# 12-USB_Phy.net
KiCad netlist of a schematic drawn in Altium Designer
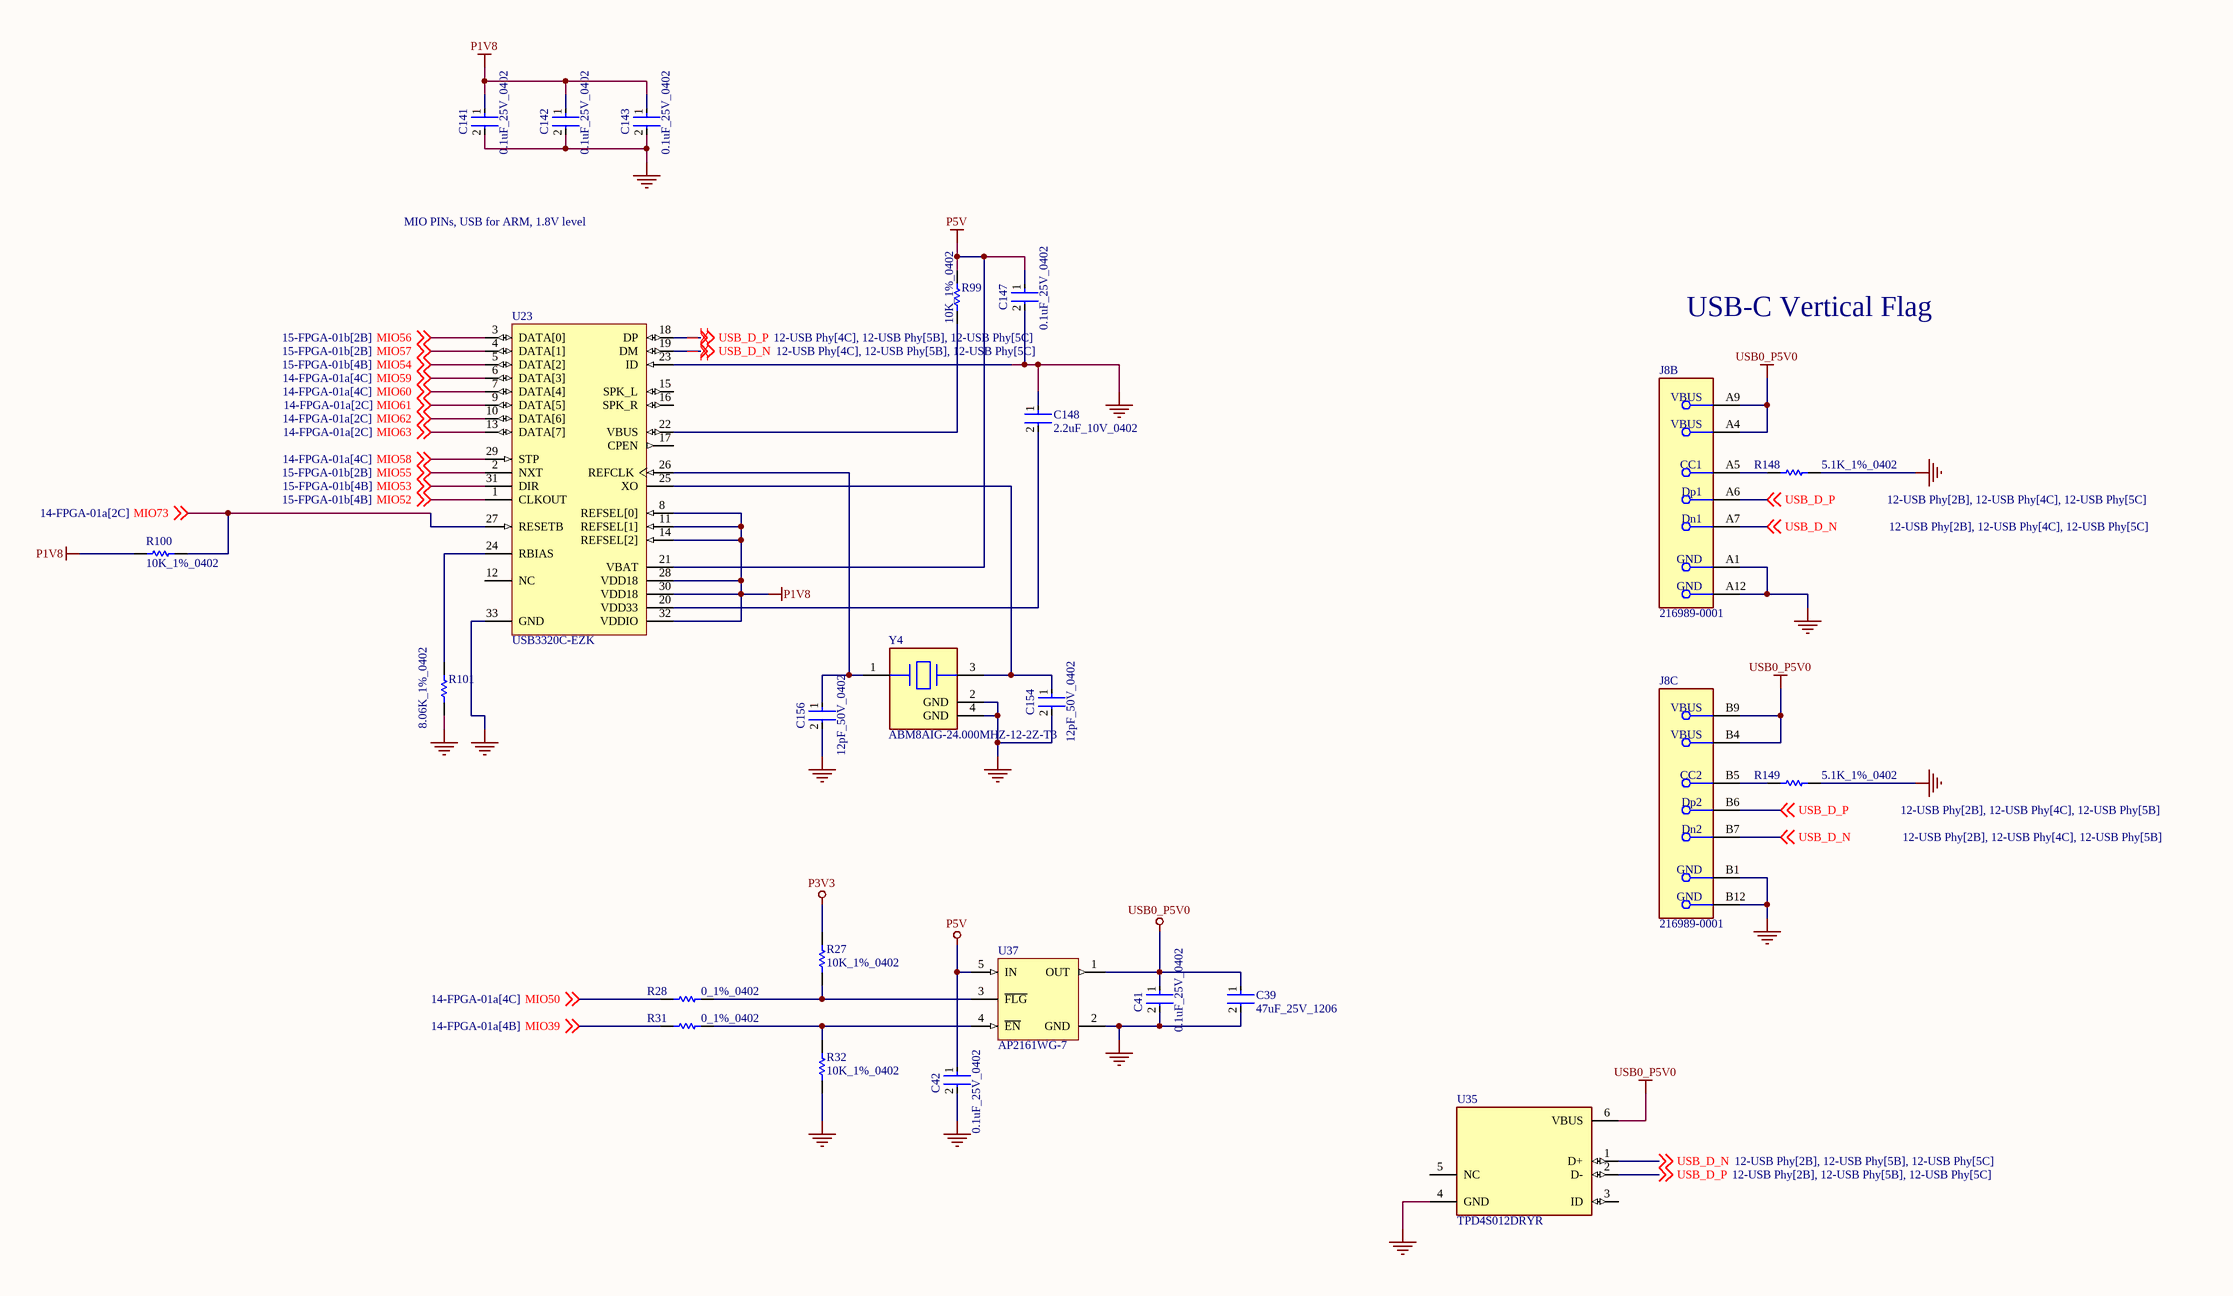
[diagram p0: 12-USB Phy.SchDoc]

(export (version "E")
  (design (tool "Eeschema 10.0.6"))
  (components
    (comp (ref "C39")
      (value "47uF_25V_1206")
      (footprint "FP-C3216-160-0_2-MFG")
      (description "Multilayer Ceramic Capacitors 47uF ±20% 25V X5R SMD 1206")
      (fields (field (name "VOLTAGE") "25V") (field (name "TOLERANCE") "20%"))
      (libsource (lib "Altium Content Vault") (part "11868f565c42a9108669ba33697ecf6"))
    )
    (comp (ref "C41")
      (value "0.1uF_25V_0402")
      (footprint "FP-0402-L_1_0_1-W_0_5_0_1-IPC_C")
      (description "General Purpose Ceramic Capacitor, 0402, 100nF, 10%, X7R, 15%, 25V")
      (fields (field (name "VOLTAGE") "25V") (field (name "TOLERANCE") "10%"))
      (libsource (lib "Altium Content Vault") (part "b4654b650e69147ec39a6b967a45e02"))
    )
    (comp (ref "C42")
      (value "0.1uF_25V_0402")
      (footprint "FP-0402-L_1_0_1-W_0_5_0_1-IPC_C")
      (description "General Purpose Ceramic Capacitor, 0402, 100nF, 10%, X7R, 15%, 25V")
      (fields (field (name "VOLTAGE") "25V") (field (name "TOLERANCE") "10%"))
      (libsource (lib "Altium Content Vault") (part "b4654b650e69147ec39a6b967a45e02"))
    )
    (comp (ref "C141")
      (value "0.1uF_25V_0402")
      (footprint "FP-0402-L_1_0_1-W_0_5_0_1-IPC_C")
      (description "General Purpose Ceramic Capacitor, 0402, 100nF, 10%, X7R, 15%, 25V")
      (fields (field (name "VOLTAGE") "25V") (field (name "TOLERANCE") "10%"))
      (libsource (lib "Altium Content Vault") (part "b4654b650e69147ec39a6b967a45e02"))
    )
    (comp (ref "C142")
      (value "0.1uF_25V_0402")
      (footprint "FP-0402-L_1_0_1-W_0_5_0_1-IPC_C")
      (description "General Purpose Ceramic Capacitor, 0402, 100nF, 10%, X7R, 15%, 25V")
      (fields (field (name "VOLTAGE") "25V") (field (name "TOLERANCE") "10%"))
      (libsource (lib "Altium Content Vault") (part "b4654b650e69147ec39a6b967a45e02"))
    )
    (comp (ref "C143")
      (value "0.1uF_25V_0402")
      (footprint "FP-0402-L_1_0_1-W_0_5_0_1-IPC_C")
      (description "General Purpose Ceramic Capacitor, 0402, 100nF, 10%, X7R, 15%, 25V")
      (fields (field (name "VOLTAGE") "25V") (field (name "TOLERANCE") "10%"))
      (libsource (lib "Altium Content Vault") (part "b4654b650e69147ec39a6b967a45e02"))
    )
    (comp (ref "C147")
      (value "0.1uF_25V_0402")
      (footprint "FP-0402-L_1_0_1-W_0_5_0_1-IPC_C")
      (description "General Purpose Ceramic Capacitor, 0402, 100nF, 10%, X7R, 15%, 25V")
      (fields (field (name "VOLTAGE") "25V") (field (name "TOLERANCE") "10%"))
      (libsource (lib "Altium Content Vault") (part "b4654b650e69147ec39a6b967a45e02"))
    )
    (comp (ref "C148")
      (value "2.2uF_10V_0402")
      (footprint "FP-C1005-050-0_15-0_1-MFG")
      (description "CAP CER 2.2UF 10V X7S 0402")
      (fields (field (name "TOLERANCE") "10%"))
      (libsource (lib "Altium Content Vault") (part "b4654b650e69147ec39a6b967a45e02"))
    )
    (comp (ref "C154")
      (value "12pF_50V_0402")
      (footprint "FP-0402-L_1_0_1-W_0_5_0_1-IPC_B")
      (description "General Purpose Ceramic Capacitor, 0402, 12pF, 5%, C0G, 30ppm/°C, 50V")
      (fields (field (name "VOLTAGE") "50V") (field (name "TOLERANCE") "5%"))
      (libsource (lib "Altium Content Vault") (part "b4654b650e69147ec39a6b967a45e02"))
    )
    (comp (ref "C156")
      (value "12pF_50V_0402")
      (footprint "FP-0402-L_1_0_1-W_0_5_0_1-IPC_B")
      (description "General Purpose Ceramic Capacitor, 0402, 12pF, 5%, C0G, 30ppm/°C, 50V")
      (fields (field (name "VOLTAGE") "50V") (field (name "TOLERANCE") "5%"))
      (libsource (lib "Altium Content Vault") (part "b4654b650e69147ec39a6b967a45e02"))
    )
    (comp (ref "J8")
      (value "216989-0001")
      (footprint "FP-216989-0001-MFG")
      (description "CONN RCPT USB2.0 TYPE C 24POS RA")
      (libsource (lib "Altium Content Vault") (part "0223f526f2db1734dda50670d79969c"))
    )
    (comp (ref "R27")
      (value "10K_1%_0402")
      (footprint "RESC1005X40X25NL10T10")
      (fields (field (name "MANUFACTURER") "Bourns") (field (name "PART NUMBER") "CR0402-FX-1002GLF"))
      (libsource (lib "Altium Content Vault") (part "RES"))
    )
    (comp (ref "R28")
      (value "0_1%_0402")
      (footprint "RESC1005X40X25LL05T05")
      (description "Chip Resistor, 0 Ohm, 0.1 W, -55 to 155 degC, 0402 (1005 Metric), RoHS, Tape and Reel")
      (fields (field (name "MANUFACTURER") "Panasonic") (field (name "TOLERANCE") "5%"))
      (libsource (lib "Altium Content Vault") (part "RES-2"))
    )
    (comp (ref "R31")
      (value "0_1%_0402")
      (footprint "RESC1005X40X25LL05T05")
      (description "Chip Resistor, 0 Ohm, 0.1 W, -55 to 155 degC, 0402 (1005 Metric), RoHS, Tape and Reel")
      (fields (field (name "MANUFACTURER") "Panasonic") (field (name "TOLERANCE") "5%"))
      (libsource (lib "Altium Content Vault") (part "RES-2"))
    )
    (comp (ref "R32")
      (value "10K_1%_0402")
      (footprint "RESC1005X40X25NL10T10")
      (fields (field (name "MANUFACTURER") "Bourns") (field (name "PART NUMBER") "CR0402-FX-1002GLF"))
      (libsource (lib "Altium Content Vault") (part "RES"))
    )
    (comp (ref "R99")
      (value "10K_1%_0402")
      (footprint "RESC1005X40X25NL10T10")
      (fields (field (name "MANUFACTURER") "Bourns") (field (name "PART NUMBER") "CR0402-FX-1002GLF"))
      (libsource (lib "Altium Content Vault") (part "RES"))
    )
    (comp (ref "R100")
      (value "10K_1%_0402")
      (footprint "RESC1005X40X25NL10T10")
      (fields (field (name "MANUFACTURER") "Bourns") (field (name "PART NUMBER") "CR0402-FX-1002GLF"))
      (libsource (lib "Altium Content Vault") (part "RES"))
    )
    (comp (ref "R101")
      (value "8.06K_1%_0402")
      (footprint "RESC1005X40X25ML05T05")
      (description "Chip Resistor, 8.06 KOhm, +/- 1%, 63 mW, -55 to 155 degC, 0402 (1005 Metric), RoHS, Tape and Reel")
      (fields (field (name "PARTNUMBER") "CRCW04028K06FKED") (field (name "TOLERANCE") "1%"))
      (libsource (lib "Altium Content Vault") (part "RES-2"))
    )
    (comp (ref "R148")
      (value "5.1K_1%_0402")
      (footprint "RESC1005X40X25ML10T10")
      (fields (field (name "MANUFACTURER") "KOA Speer") (field (name "PART NUMBER") "RK73H1ETTP5101F"))
      (libsource (lib "Altium Content Vault") (part "RES"))
    )
    (comp (ref "R149")
      (value "5.1K_1%_0402")
      (footprint "RESC1005X40X25ML10T10")
      (fields (field (name "MANUFACTURER") "KOA Speer") (field (name "PART NUMBER") "RK73H1ETTP5101F"))
      (libsource (lib "Altium Content Vault") (part "RES"))
    )
    (comp (ref "U23")
      (value "USB3320C-EZK")
      (footprint "MCHP-QFN-32-5x5_V2")
      (fields (field (name "MANUFACTURER") "Microchip"))
      (libsource (lib "Altium Content Vault") (part "MCHP-USB3320-32"))
    )
    (comp (ref "U35")
      (value "TPD4S012DRYR")
      (footprint "FP-DRY0006A-MFG")
      (description "TVS DIODE 5.5V 6SON")
      (libsource (lib "Altium Content Vault") (part "0f51f1bc734c3fed0021f16fcfaf2e1"))
    )
    (comp (ref "U37")
      (value "AP2161WG-7")
      (footprint "DIOD-SOT25-5_V")
      (fields (field (name "MANUFACTURER") "Diodes-Incorporated"))
      (libsource (lib "Altium Content Vault") (part "DIOD-AP2161-SOT25-5"))
    )
    (comp (ref "Y4")
      (value "ABM8AIG-24.000MHZ-12-2Z-T3")
      (footprint "FP-ABM8AIG-MFG")
      (description "Crystal 24MHz ±20ppm (Tol) ±50ppm (Stability) 12pF FUND 50Ω Automotive 4-Pin Ultra Mini-CSMD T/R")
      (libsource (lib "Altium Content Vault") (part "5645ab55de99a04feaa93ac4102b7fe"))
    )
  )
  (nets
    (net (code "1") (name "GND") (class "Default")
      (node (ref "C141") (pin "2") (pinfunction "2_2") (pintype "passive"))
      (node (ref "C142") (pin "2") (pinfunction "2_2") (pintype "passive"))
      (node (ref "C143") (pin "2") (pinfunction "2_2") (pintype "passive"))
      (node (ref "C147") (pin "2") (pinfunction "2_2") (pintype "passive"))
      (node (ref "C148") (pin "1") (pinfunction "1_1") (pintype "passive"))
      (node (ref "C154") (pin "2") (pinfunction "2_2") (pintype "passive"))
      (node (ref "C156") (pin "2") (pinfunction "2_2") (pintype "passive"))
      (node (ref "C39") (pin "2") (pinfunction "2_2") (pintype "passive"))
      (node (ref "C41") (pin "2") (pinfunction "2_2") (pintype "passive"))
      (node (ref "C42") (pin "2") (pinfunction "2_2") (pintype "passive"))
      (node (ref "J8") (pin "A1") (pinfunction "GND_A1") (pintype "power_in"))
      (node (ref "J8") (pin "A12") (pinfunction "GND_A12") (pintype "power_in"))
      (node (ref "J8") (pin "B1") (pinfunction "GND_B1") (pintype "power_in"))
      (node (ref "J8") (pin "B12") (pinfunction "GND_B12") (pintype "power_in"))
      (node (ref "R101") (pin "1") (pinfunction "1_1") (pintype "passive"))
      (node (ref "R148") (pin "2") (pinfunction "2_2") (pintype "passive"))
      (node (ref "R149") (pin "2") (pinfunction "2_2") (pintype "passive"))
      (node (ref "R32") (pin "1") (pinfunction "1_1") (pintype "passive"))
      (node (ref "U23") (pin "23") (pinfunction "ID_23") (pintype "input"))
      (node (ref "U23") (pin "33") (pinfunction "GND_33") (pintype "power_in"))
      (node (ref "U35") (pin "4") (pinfunction "GND_4") (pintype "power_in"))
      (node (ref "U37") (pin "2") (pinfunction "GND_2") (pintype "power_in"))
      (node (ref "Y4") (pin "2") (pinfunction "GND_2") (pintype "power_in"))
      (node (ref "Y4") (pin "4") (pinfunction "GND_4") (pintype "power_in"))
    )
    (net (code "2") (name "MIO39") (class "Default")
      (node (ref "R31") (pin "1") (pinfunction "1_1") (pintype "passive"))
    )
    (net (code "3") (name "MIO50") (class "Default")
      (node (ref "R28") (pin "1") (pinfunction "1_1") (pintype "passive"))
    )
    (net (code "4") (name "MIO52") (class "Default")
      (node (ref "U23") (pin "1") (pinfunction "CLKOUT_1") (pintype "tri_state"))
    )
    (net (code "5") (name "MIO53") (class "Default")
      (node (ref "U23") (pin "31") (pinfunction "DIR_31") (pintype "tri_state"))
    )
    (net (code "6") (name "MIO54") (class "Default")
      (node (ref "U23") (pin "5") (pinfunction "DATA[2]_5") (pintype "bidirectional"))
    )
    (net (code "7") (name "MIO55") (class "Default")
      (node (ref "U23") (pin "2") (pinfunction "NXT_2") (pintype "tri_state"))
    )
    (net (code "8") (name "MIO56") (class "Default")
      (node (ref "U23") (pin "3") (pinfunction "DATA[0]_3") (pintype "bidirectional"))
    )
    (net (code "9") (name "MIO57") (class "Default")
      (node (ref "U23") (pin "4") (pinfunction "DATA[1]_4") (pintype "bidirectional"))
    )
    (net (code "10") (name "MIO58") (class "Default")
      (node (ref "U23") (pin "29") (pinfunction "STP_29") (pintype "input"))
    )
    (net (code "11") (name "MIO59") (class "Default")
      (node (ref "U23") (pin "6") (pinfunction "DATA[3]_6") (pintype "bidirectional"))
    )
    (net (code "12") (name "MIO60") (class "Default")
      (node (ref "U23") (pin "7") (pinfunction "DATA[4]_7") (pintype "bidirectional"))
    )
    (net (code "13") (name "MIO61") (class "Default")
      (node (ref "U23") (pin "9") (pinfunction "DATA[5]_9") (pintype "bidirectional"))
    )
    (net (code "14") (name "MIO62") (class "Default")
      (node (ref "U23") (pin "10") (pinfunction "DATA[6]_10") (pintype "bidirectional"))
    )
    (net (code "15") (name "MIO63") (class "Default")
      (node (ref "U23") (pin "13") (pinfunction "DATA[7]_13") (pintype "bidirectional"))
    )
    (net (code "16") (name "MIO73") (class "Default")
      (node (ref "R100") (pin "2") (pinfunction "2_2") (pintype "passive"))
      (node (ref "U23") (pin "27") (pinfunction "RESETB_27") (pintype "input"))
    )
    (net (code "17") (name "Net-(J8B-CC1)") (class "Default")
      (node (ref "J8") (pin "A5") (pinfunction "CC1_A5") (pintype "passive"))
      (node (ref "R148") (pin "1") (pinfunction "1_1") (pintype "passive"))
    )
    (net (code "18") (name "Net-(J8C-CC2)") (class "Default")
      (node (ref "J8") (pin "B5") (pinfunction "CC2_B5") (pintype "passive"))
      (node (ref "R149") (pin "1") (pinfunction "1_1") (pintype "passive"))
    )
    (net (code "19") (name "Net-(U23-RBIAS)") (class "Default")
      (node (ref "R101") (pin "2") (pinfunction "2_2") (pintype "passive"))
      (node (ref "U23") (pin "24") (pinfunction "RBIAS_24") (pintype "passive"))
    )
    (net (code "20") (name "Net-(U23-REFCLK)") (class "Default")
      (node (ref "C156") (pin "1") (pinfunction "1_1") (pintype "passive"))
      (node (ref "U23") (pin "26") (pinfunction "REFCLK_26") (pintype "input"))
      (node (ref "Y4") (pin "1") (pinfunction "1_1") (pintype "passive"))
    )
    (net (code "21") (name "Net-(U23-VBUS)") (class "Default")
      (node (ref "R99") (pin "1") (pinfunction "1_1") (pintype "passive"))
      (node (ref "U23") (pin "22") (pinfunction "VBUS_22") (pintype "bidirectional"))
    )
    (net (code "22") (name "Net-(U23-VDD33)") (class "Default")
      (node (ref "C148") (pin "2") (pinfunction "2_2") (pintype "passive"))
      (node (ref "U23") (pin "20") (pinfunction "VDD33_20") (pintype "power_in"))
    )
    (net (code "23") (name "Net-(U23-XO)") (class "Default")
      (node (ref "C154") (pin "1") (pinfunction "1_1") (pintype "passive"))
      (node (ref "U23") (pin "25") (pinfunction "XO_25") (pintype "passive"))
      (node (ref "Y4") (pin "3") (pinfunction "3_3") (pintype "passive"))
    )
    (net (code "24") (name "Net-(U37-~{EN})") (class "Default")
      (node (ref "R31") (pin "2") (pinfunction "2_2") (pintype "passive"))
      (node (ref "R32") (pin "2") (pinfunction "2_2") (pintype "passive"))
      (node (ref "U37") (pin "4") (pinfunction "~{EN}_4") (pintype "input"))
    )
    (net (code "25") (name "Net-(U37-~{FLG})") (class "Default")
      (node (ref "R27") (pin "1") (pinfunction "1_1") (pintype "passive"))
      (node (ref "R28") (pin "2") (pinfunction "2_2") (pintype "passive"))
      (node (ref "U37") (pin "3") (pinfunction "~{FLG}_3") (pintype "open_collector"))
    )
    (net (code "26") (name "P1V8") (class "Default")
      (node (ref "C141") (pin "1") (pinfunction "1_1") (pintype "passive"))
      (node (ref "C142") (pin "1") (pinfunction "1_1") (pintype "passive"))
      (node (ref "C143") (pin "1") (pinfunction "1_1") (pintype "passive"))
      (node (ref "R100") (pin "1") (pinfunction "1_1") (pintype "passive"))
      (node (ref "U23") (pin "11") (pinfunction "REFSEL[1]_11") (pintype "input"))
      (node (ref "U23") (pin "14") (pinfunction "REFSEL[2]_14") (pintype "input"))
      (node (ref "U23") (pin "28") (pinfunction "VDD18_28") (pintype "power_in"))
      (node (ref "U23") (pin "30") (pinfunction "VDD18_30") (pintype "power_in"))
      (node (ref "U23") (pin "32") (pinfunction "VDDIO_32") (pintype "power_in"))
      (node (ref "U23") (pin "8") (pinfunction "REFSEL[0]_8") (pintype "input"))
    )
    (net (code "27") (name "P3V3") (class "Default")
      (node (ref "R27") (pin "2") (pinfunction "2_2") (pintype "passive"))
    )
    (net (code "28") (name "P5V") (class "Default")
      (node (ref "C147") (pin "1") (pinfunction "1_1") (pintype "passive"))
      (node (ref "C42") (pin "1") (pinfunction "1_1") (pintype "passive"))
      (node (ref "R99") (pin "2") (pinfunction "2_2") (pintype "passive"))
      (node (ref "U23") (pin "21") (pinfunction "VBAT_21") (pintype "power_in"))
      (node (ref "U37") (pin "5") (pinfunction "IN_5") (pintype "input"))
    )
    (net (code "29") (name "USB0_P5V0") (class "Default")
      (node (ref "C39") (pin "1") (pinfunction "1_1") (pintype "passive"))
      (node (ref "C41") (pin "1") (pinfunction "1_1") (pintype "passive"))
      (node (ref "J8") (pin "A4") (pinfunction "VBUS_A4") (pintype "passive"))
      (node (ref "J8") (pin "A9") (pinfunction "VBUS_A9") (pintype "power_in"))
      (node (ref "J8") (pin "B4") (pinfunction "VBUS_B4") (pintype "passive"))
      (node (ref "J8") (pin "B9") (pinfunction "VBUS_B9") (pintype "passive"))
      (node (ref "U35") (pin "6") (pinfunction "VBUS_6") (pintype "passive"))
      (node (ref "U37") (pin "1") (pinfunction "OUT_1") (pintype "output"))
    )
    (net (code "30") (name "USB_D_N") (class "Default")
      (node (ref "J8") (pin "A7") (pinfunction "Dn1_A7") (pintype "passive"))
      (node (ref "J8") (pin "B7") (pinfunction "Dn2_B7") (pintype "passive"))
      (node (ref "U23") (pin "19") (pinfunction "DM_19") (pintype "bidirectional"))
      (node (ref "U35") (pin "1") (pinfunction "D+_1") (pintype "bidirectional"))
    )
    (net (code "31") (name "USB_D_P") (class "Default")
      (node (ref "J8") (pin "A6") (pinfunction "Dp1_A6") (pintype "passive"))
      (node (ref "J8") (pin "B6") (pinfunction "Dp2_B6") (pintype "passive"))
      (node (ref "U23") (pin "18") (pinfunction "DP_18") (pintype "bidirectional"))
      (node (ref "U35") (pin "2") (pinfunction "D-_2") (pintype "bidirectional"))
    )
    (net (code "32") (name "unconnected-(U23-CPEN-Pad17)") (class "Default")
      (node (ref "U23") (pin "17") (pinfunction "CPEN_17") (pintype "output"))
    )
    (net (code "33") (name "unconnected-(U23-NC-Pad12)") (class "Default")
      (node (ref "U23") (pin "12") (pinfunction "NC_12") (pintype "passive"))
    )
    (net (code "34") (name "unconnected-(U23-SPK_L-Pad15)") (class "Default")
      (node (ref "U23") (pin "15") (pinfunction "SPK_L_15") (pintype "bidirectional"))
    )
    (net (code "35") (name "unconnected-(U23-SPK_R-Pad16)") (class "Default")
      (node (ref "U23") (pin "16") (pinfunction "SPK_R_16") (pintype "bidirectional"))
    )
    (net (code "36") (name "unconnected-(U35-ID-Pad3)") (class "Default")
      (node (ref "U35") (pin "3") (pinfunction "ID_3") (pintype "bidirectional"))
    )
    (net (code "37") (name "unconnected-(U35-NC-Pad5)") (class "Default")
      (node (ref "U35") (pin "5") (pinfunction "NC_5") (pintype "passive"))
    )
  )
)
